# schematic.net
KiCad netlist of a schematic drawn in EasyEDA
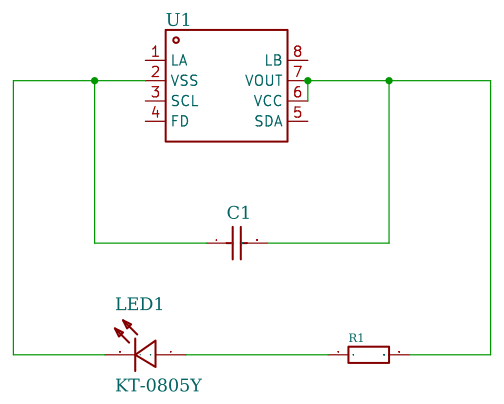
[diagram p0: schematic sheet]

(export (version "E")
  (design (tool "Eeschema 10.0.6"))
  (components
    (comp (ref "C1")
      (value "220nF")
      (fields
        (field (name "Manufacturer Part") "CL10B224KA8NNNC")
        (field (name "Manufacturer") "SAMSUNG(三星)")
      )
      (libsource (lib "") (part "Unknown_615_-510"))
    )
    (comp (ref "LED1")
      (value "KT-0805Y")
      (fields (field (name "Manufacturer") "KENTO"))
      (libsource (lib "") (part "Unknown_570_-455"))
    )
    (comp (ref "R1")
      (value "47Ω")
      (fields
        (field (name "Manufacturer Part") "0603WAF470JT5E")
        (field (name "Manufacturer") "UNI-ROYAL(厚声)")
      )
      (libsource (lib "") (part "Unknown_680_-455"))
    )
    (comp (ref "U1")
      (value "13.56MHz")
      (fields (field (name "Manufacturer Part") "NT3H2111W0FHKH") (field (name "Manufacturer") "NXP(恩智浦)"))
      (libsource (lib "") (part "Unknown_610_-585"))
    )
  )
  (nets
    (net (code "1") (name "Net-(LED1-+)") (class "Default")
      (node (ref "LED1") (pin "1") (pinfunction "+_1") (pintype "unspecified"))
      (node (ref "R1") (pin "1") (pinfunction "1_1") (pintype "unspecified"))
    )
    (net (code "2") (name "Net-(LED1--)") (class "Default")
      (node (ref "C1") (pin "1") (pinfunction "1_1") (pintype "unspecified"))
      (node (ref "LED1") (pin "2") (pinfunction "-_2") (pintype "unspecified"))
      (node (ref "U1") (pin "2") (pinfunction "VSS_2") (pintype "unspecified"))
    )
    (net (code "3") (name "Net-(U1-VCC)") (class "Default")
      (node (ref "C1") (pin "2") (pinfunction "2_2") (pintype "unspecified"))
      (node (ref "R1") (pin "2") (pinfunction "2_2") (pintype "unspecified"))
      (node (ref "U1") (pin "6") (pinfunction "VCC_6") (pintype "unspecified"))
      (node (ref "U1") (pin "7") (pinfunction "VOUT_7") (pintype "unspecified"))
    )
    (net (code "4") (name "unconnected-(U1-FD-Pad4)") (class "Default")
      (node (ref "U1") (pin "4") (pinfunction "FD_4") (pintype "unspecified"))
    )
    (net (code "5") (name "unconnected-(U1-LA-Pad1)") (class "Default")
      (node (ref "U1") (pin "1") (pinfunction "LA_1") (pintype "unspecified"))
    )
    (net (code "6") (name "unconnected-(U1-LB-Pad8)") (class "Default")
      (node (ref "U1") (pin "8") (pinfunction "LB_8") (pintype "unspecified"))
    )
    (net (code "7") (name "unconnected-(U1-SCL-Pad3)") (class "Default")
      (node (ref "U1") (pin "3") (pinfunction "SCL_3") (pintype "unspecified"))
    )
    (net (code "8") (name "unconnected-(U1-SDA-Pad5)") (class "Default")
      (node (ref "U1") (pin "5") (pinfunction "SDA_5") (pintype "unspecified"))
    )
  )
)
